# Quasar_v0_1.net
KiCad netlist of a schematic drawn in EAGLE
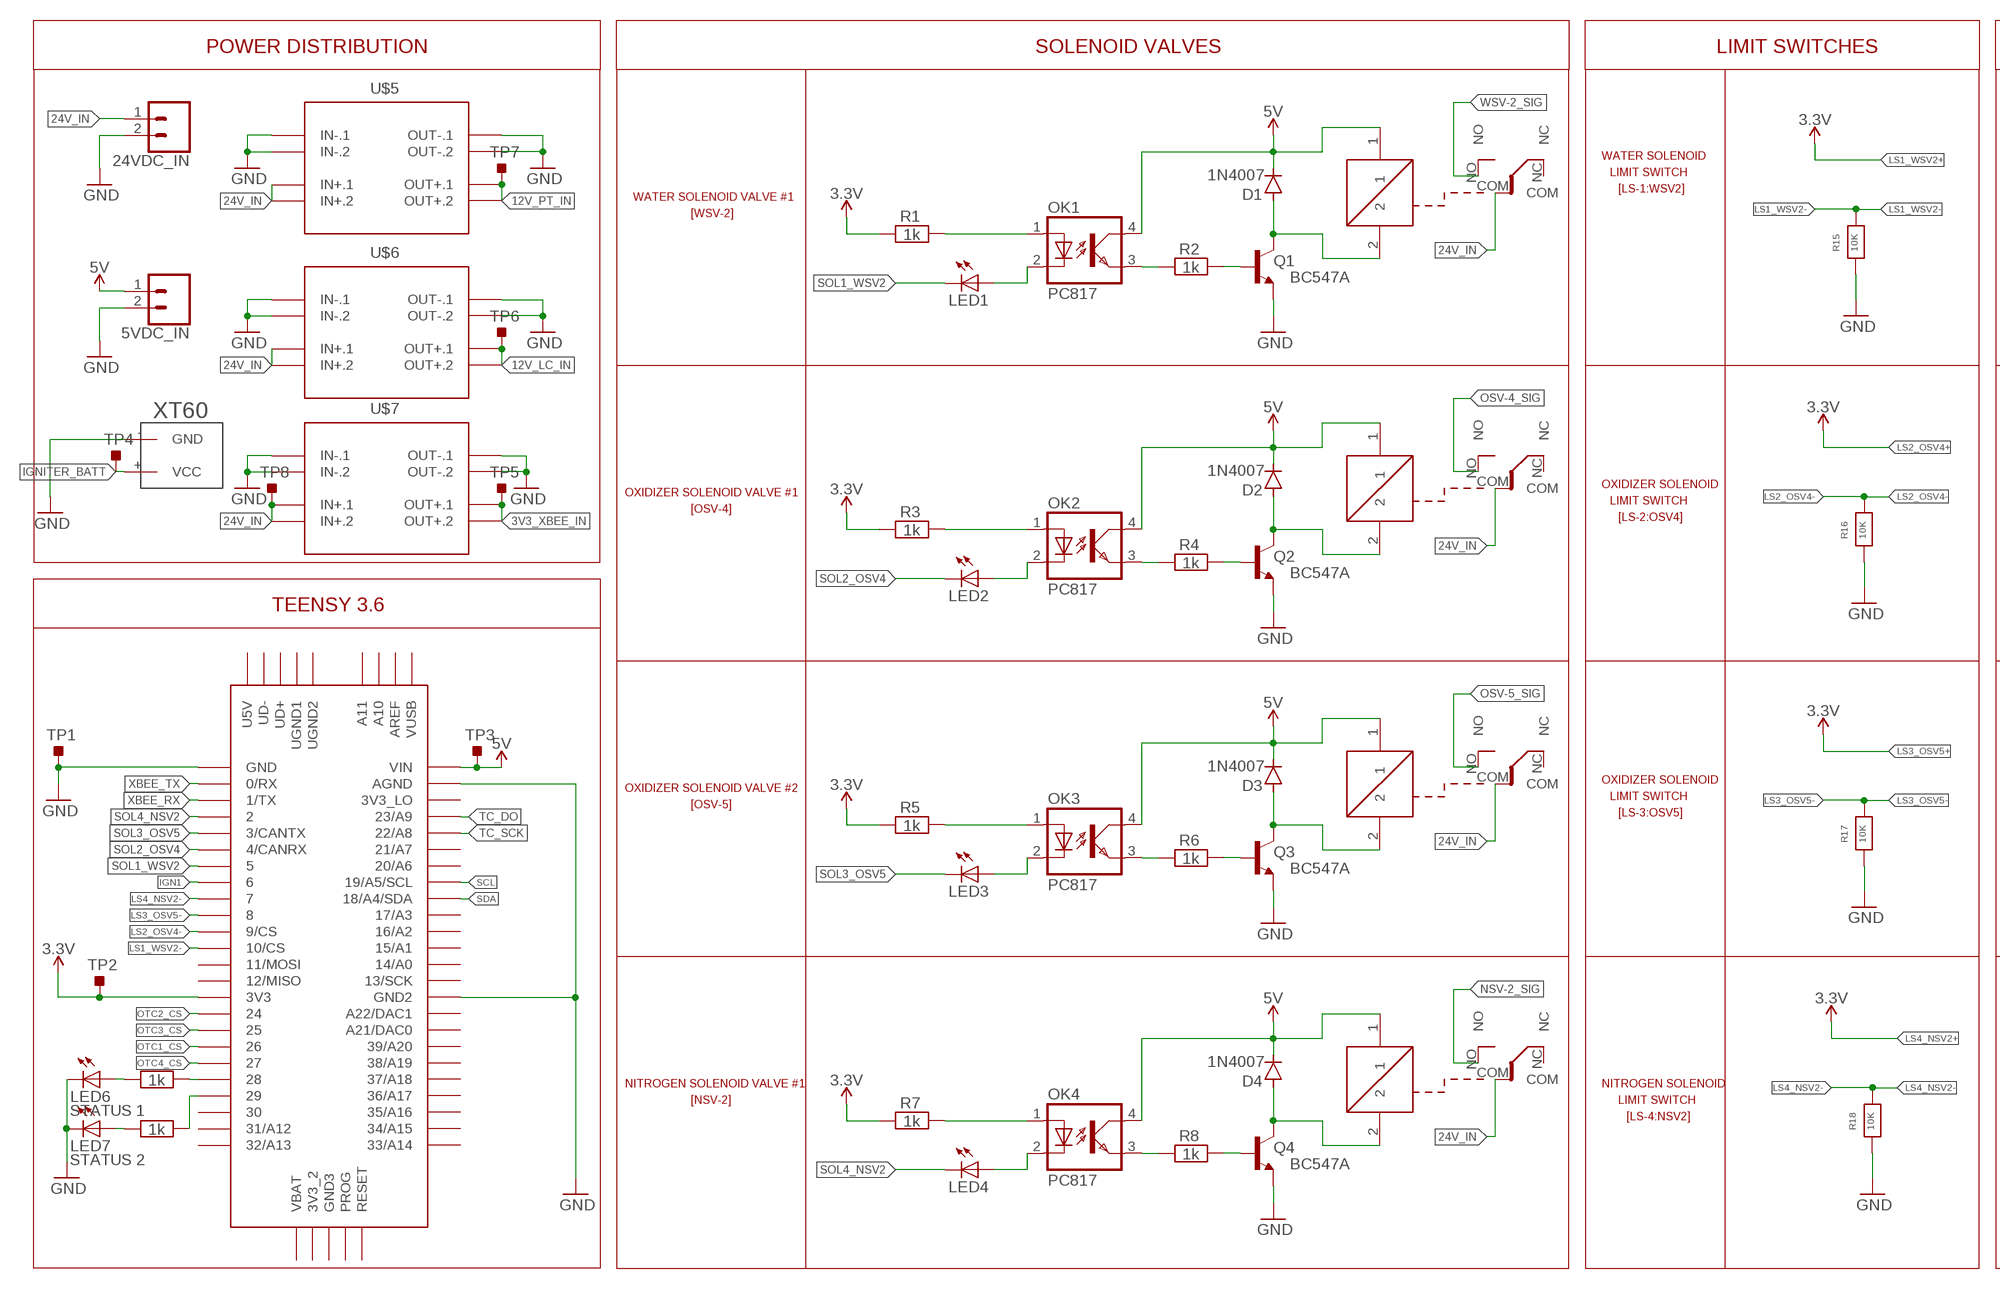
[diagram p0: schematic, sheet 1, part 1 of 2]
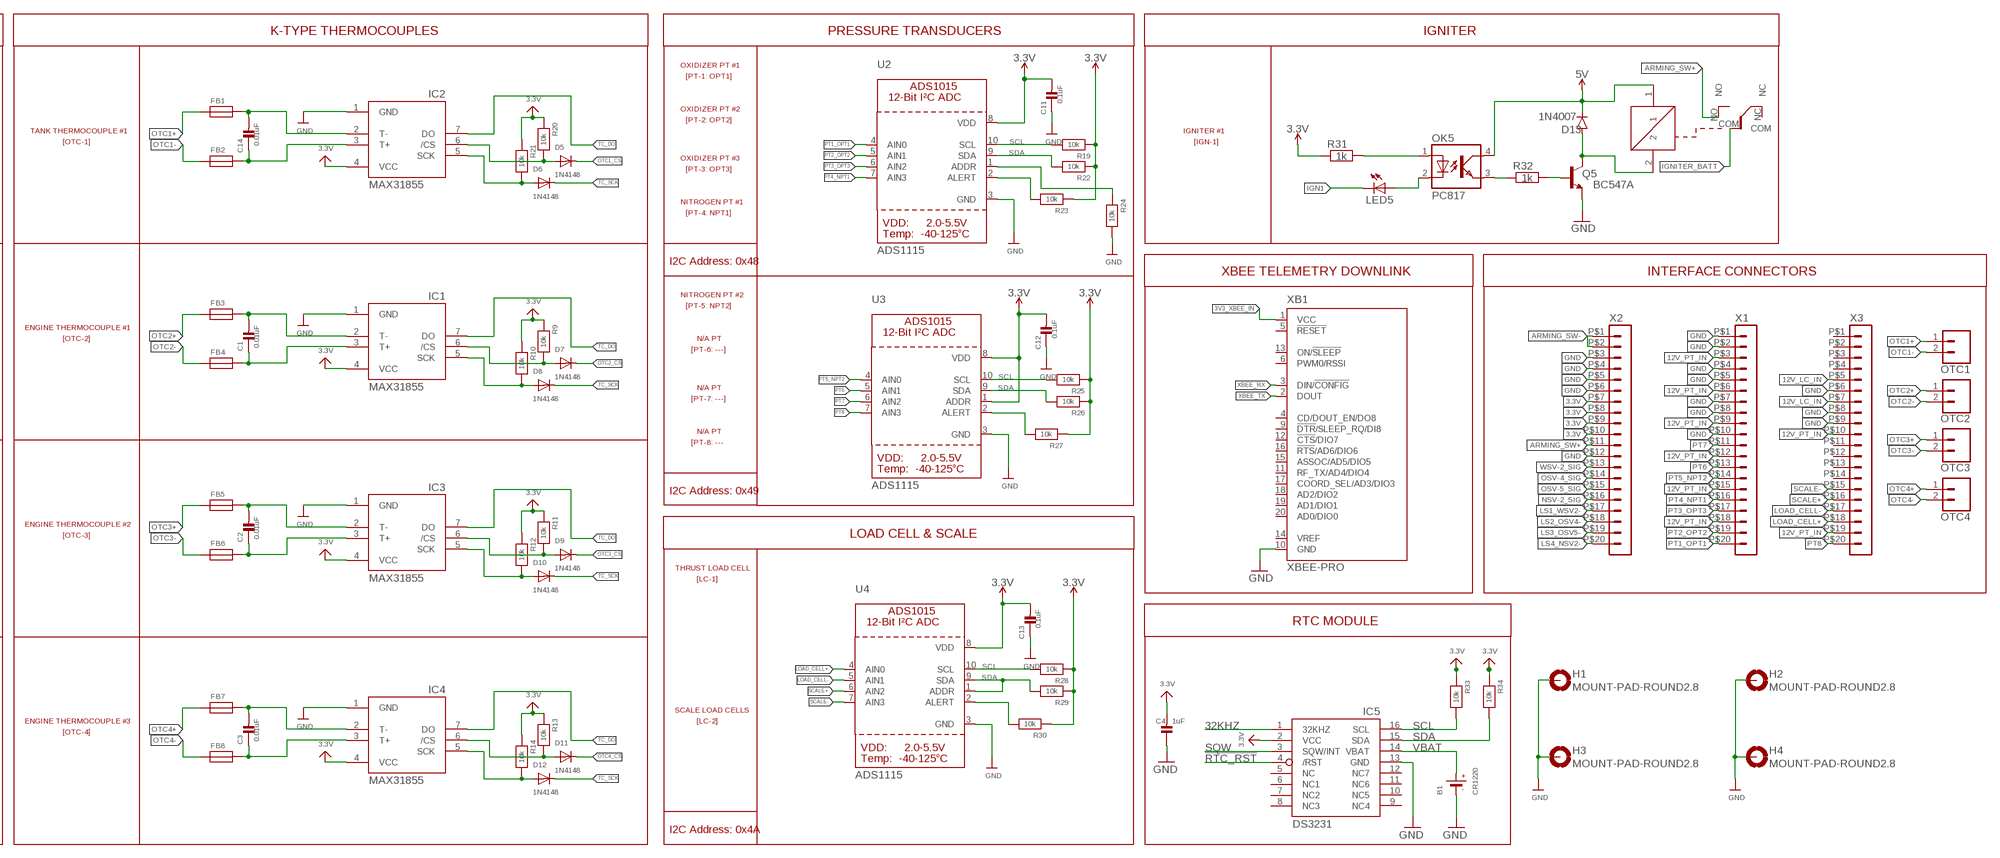
[diagram p1: schematic, sheet 1, part 2 of 2]

(export (version "E")
  (design (tool "Eeschema 10.0.6"))
  (components
    (comp (ref "5VDC_IN")
      (value "CONN_025MM")
      (footprint "eagle-import:SCREWTERMINAL-5MM-2")
      (libsource (lib "eagle-import") (part "CONN_025MM"))
    )
    (comp (ref "24VDC_IN")
      (value "CONN_025MM")
      (footprint "eagle-import:SCREWTERMINAL-5MM-2")
      (libsource (lib "eagle-import") (part "CONN_025MM"))
    )
    (comp (ref "B1")
      (value "CR1220")
      (footprint "eagle-import:CR1220")
      (libsource (lib "eagle-import") (part "BATTERYCR1220_SMT"))
    )
    (comp (ref "C1")
      (value "0.01uF")
      (footprint "eagle-import:0805")
      (libsource (lib "eagle-import") (part "CAP_CERAMIC0805"))
    )
    (comp (ref "C2")
      (value "0.01uF")
      (footprint "eagle-import:0805")
      (libsource (lib "eagle-import") (part "CAP_CERAMIC0805"))
    )
    (comp (ref "C3")
      (value "0.01uF")
      (footprint "eagle-import:0805")
      (libsource (lib "eagle-import") (part "CAP_CERAMIC0805"))
    )
    (comp (ref "C4")
      (value "1uF")
      (footprint "eagle-import:0805")
      (libsource (lib "eagle-import") (part "CAP_CERAMIC0805"))
    )
    (comp (ref "C11")
      (value "0.1uF")
      (footprint "eagle-import:0805")
      (libsource (lib "eagle-import") (part "CAP_CERAMIC0805"))
    )
    (comp (ref "C12")
      (value "0.1uF")
      (footprint "eagle-import:0805")
      (libsource (lib "eagle-import") (part "CAP_CERAMIC0805"))
    )
    (comp (ref "C13")
      (value "0.1uF")
      (footprint "eagle-import:0805")
      (libsource (lib "eagle-import") (part "CAP_CERAMIC0805"))
    )
    (comp (ref "C14")
      (value "0.01uF")
      (footprint "eagle-import:0805")
      (libsource (lib "eagle-import") (part "CAP_CERAMIC0805"))
    )
    (comp (ref "D1")
      (value "1N4007")
      (footprint "eagle-import:DO-41")
      (fields
        (field (name "DIGIKEY_PART_NUMBER") "1N4007MSCT-ND")
        (field (name "MANUFACTURER") "Micro Commercial Co")
        (field (name "CREATED_BY") "PCBLayout.com")
      )
      (libsource (lib "eagle-import") (part "1N4007"))
    )
    (comp (ref "D2")
      (value "1N4007")
      (footprint "eagle-import:DO-41")
      (fields
        (field (name "DIGIKEY_PART_NUMBER") "1N4007MSCT-ND")
        (field (name "MANUFACTURER") "Micro Commercial Co")
        (field (name "CREATED_BY") "PCBLayout.com")
      )
      (libsource (lib "eagle-import") (part "1N4007"))
    )
    (comp (ref "D3")
      (value "1N4007")
      (footprint "eagle-import:DO-41")
      (fields
        (field (name "DIGIKEY_PART_NUMBER") "1N4007MSCT-ND")
        (field (name "MANUFACTURER") "Micro Commercial Co")
        (field (name "CREATED_BY") "PCBLayout.com")
      )
      (libsource (lib "eagle-import") (part "1N4007"))
    )
    (comp (ref "D4")
      (value "1N4007")
      (footprint "eagle-import:DO-41")
      (fields
        (field (name "DIGIKEY_PART_NUMBER") "1N4007MSCT-ND")
        (field (name "MANUFACTURER") "Micro Commercial Co")
        (field (name "CREATED_BY") "PCBLayout.com")
      )
      (libsource (lib "eagle-import") (part "1N4007"))
    )
    (comp (ref "D5")
      (value "1N4148")
      (footprint "eagle-import:SOD-123")
      (libsource (lib "eagle-import") (part "DIODESOD-123"))
    )
    (comp (ref "D6")
      (value "1N4148")
      (footprint "eagle-import:SOD-123")
      (libsource (lib "eagle-import") (part "DIODESOD-123"))
    )
    (comp (ref "D7")
      (value "1N4148")
      (footprint "eagle-import:SOD-123")
      (libsource (lib "eagle-import") (part "DIODESOD-123"))
    )
    (comp (ref "D8")
      (value "1N4148")
      (footprint "eagle-import:SOD-123")
      (libsource (lib "eagle-import") (part "DIODESOD-123"))
    )
    (comp (ref "D9")
      (value "1N4148")
      (footprint "eagle-import:SOD-123")
      (libsource (lib "eagle-import") (part "DIODESOD-123"))
    )
    (comp (ref "D10")
      (value "1N4148")
      (footprint "eagle-import:SOD-123")
      (libsource (lib "eagle-import") (part "DIODESOD-123"))
    )
    (comp (ref "D11")
      (value "1N4148")
      (footprint "eagle-import:SOD-123")
      (libsource (lib "eagle-import") (part "DIODESOD-123"))
    )
    (comp (ref "D12")
      (value "1N4148")
      (footprint "eagle-import:SOD-123")
      (libsource (lib "eagle-import") (part "DIODESOD-123"))
    )
    (comp (ref "D13")
      (value "1N4007")
      (footprint "eagle-import:DO-41")
      (fields
        (field (name "DIGIKEY_PART_NUMBER") "1N4007MSCT-ND")
        (field (name "MANUFACTURER") "Micro Commercial Co")
        (field (name "CREATED_BY") "PCBLayout.com")
      )
      (libsource (lib "eagle-import") (part "1N4007"))
    )
    (comp (ref "FB1")
      (value "FERRITE")
      (footprint "eagle-import:0603")
      (libsource (lib "eagle-import") (part "FERRITE"))
    )
    (comp (ref "FB2")
      (value "FERRITE")
      (footprint "eagle-import:0603")
      (libsource (lib "eagle-import") (part "FERRITE"))
    )
    (comp (ref "FB3")
      (value "FERRITE")
      (footprint "eagle-import:0603")
      (libsource (lib "eagle-import") (part "FERRITE"))
    )
    (comp (ref "FB4")
      (value "FERRITE")
      (footprint "eagle-import:0603")
      (libsource (lib "eagle-import") (part "FERRITE"))
    )
    (comp (ref "FB5")
      (value "FERRITE")
      (footprint "eagle-import:0603")
      (libsource (lib "eagle-import") (part "FERRITE"))
    )
    (comp (ref "FB6")
      (value "FERRITE")
      (footprint "eagle-import:0603")
      (libsource (lib "eagle-import") (part "FERRITE"))
    )
    (comp (ref "FB7")
      (value "FERRITE")
      (footprint "eagle-import:0603")
      (libsource (lib "eagle-import") (part "FERRITE"))
    )
    (comp (ref "FB8")
      (value "FERRITE")
      (footprint "eagle-import:0603")
      (libsource (lib "eagle-import") (part "FERRITE"))
    )
    (comp (ref "H1")
      (value "MOUNT-PAD-ROUND2.8")
      (footprint "eagle-import:2,8-PAD")
      (libsource (lib "eagle-import") (part "MOUNT-PAD-ROUND2.8"))
    )
    (comp (ref "H2")
      (value "MOUNT-PAD-ROUND2.8")
      (footprint "eagle-import:2,8-PAD")
      (libsource (lib "eagle-import") (part "MOUNT-PAD-ROUND2.8"))
    )
    (comp (ref "H3")
      (value "MOUNT-PAD-ROUND2.8")
      (footprint "eagle-import:2,8-PAD")
      (libsource (lib "eagle-import") (part "MOUNT-PAD-ROUND2.8"))
    )
    (comp (ref "H4")
      (value "MOUNT-PAD-ROUND2.8")
      (footprint "eagle-import:2,8-PAD")
      (libsource (lib "eagle-import") (part "MOUNT-PAD-ROUND2.8"))
    )
    (comp (ref "IC1")
      (value "MAX31855")
      (footprint "eagle-import:SO08")
      (libsource (lib "eagle-import") (part "MAX6675"))
    )
    (comp (ref "IC2")
      (value "MAX31855")
      (footprint "eagle-import:SO08")
      (libsource (lib "eagle-import") (part "MAX6675"))
    )
    (comp (ref "IC3")
      (value "MAX31855")
      (footprint "eagle-import:SO08")
      (libsource (lib "eagle-import") (part "MAX6675"))
    )
    (comp (ref "IC4")
      (value "MAX31855")
      (footprint "eagle-import:SO08")
      (libsource (lib "eagle-import") (part "MAX6675"))
    )
    (comp (ref "IC5")
      (value "DS3231/SO")
      (footprint "eagle-import:SO16W")
      (libsource (lib "eagle-import") (part "DS3231/SO"))
    )
    (comp (ref "LED1")
      (value "LEDCHIPLED_1206")
      (footprint "eagle-import:CHIPLED_1206")
      (libsource (lib "eagle-import") (part "adafruit_420_LEDCHIPLED_1206"))
    )
    (comp (ref "LED2")
      (value "LEDCHIPLED_1206")
      (footprint "eagle-import:CHIPLED_1206")
      (libsource (lib "eagle-import") (part "adafruit_420_LEDCHIPLED_1206"))
    )
    (comp (ref "LED3")
      (value "LEDCHIPLED_1206")
      (footprint "eagle-import:CHIPLED_1206")
      (libsource (lib "eagle-import") (part "adafruit_420_LEDCHIPLED_1206"))
    )
    (comp (ref "LED4")
      (value "LEDCHIPLED_1206")
      (footprint "eagle-import:CHIPLED_1206")
      (libsource (lib "eagle-import") (part "adafruit_420_LEDCHIPLED_1206"))
    )
    (comp (ref "LED5")
      (value "LEDCHIPLED_1206")
      (footprint "eagle-import:CHIPLED_1206")
      (libsource (lib "eagle-import") (part "adafruit_420_LEDCHIPLED_1206"))
    )
    (comp (ref "LED6")
      (value "STATUS 1")
      (footprint "eagle-import:LED5MM")
      (libsource (lib "eagle-import") (part "LED5MM"))
    )
    (comp (ref "LED7")
      (value "STATUS 2")
      (footprint "eagle-import:LED5MM")
      (libsource (lib "eagle-import") (part "LED5MM"))
    )
    (comp (ref "OK1")
      (value "PC817")
      (footprint "eagle-import:DIL04")
      (libsource (lib "eagle-import") (part "PC817"))
    )
    (comp (ref "OK2")
      (value "PC817")
      (footprint "eagle-import:DIL04")
      (libsource (lib "eagle-import") (part "PC817"))
    )
    (comp (ref "OK3")
      (value "PC817")
      (footprint "eagle-import:DIL04")
      (libsource (lib "eagle-import") (part "PC817"))
    )
    (comp (ref "OK4")
      (value "PC817")
      (footprint "eagle-import:DIL04")
      (libsource (lib "eagle-import") (part "PC817"))
    )
    (comp (ref "OK5")
      (value "PC817")
      (footprint "eagle-import:DIL04")
      (libsource (lib "eagle-import") (part "PC817"))
    )
    (comp (ref "OTC1")
      (value "CONN_025MM")
      (footprint "eagle-import:SCREWTERMINAL-5MM-2")
      (libsource (lib "eagle-import") (part "CONN_025MM"))
    )
    (comp (ref "OTC2")
      (value "CONN_025MM")
      (footprint "eagle-import:SCREWTERMINAL-5MM-2")
      (libsource (lib "eagle-import") (part "CONN_025MM"))
    )
    (comp (ref "OTC3")
      (value "CONN_025MM")
      (footprint "eagle-import:SCREWTERMINAL-5MM-2")
      (libsource (lib "eagle-import") (part "CONN_025MM"))
    )
    (comp (ref "OTC4")
      (value "CONN_025MM")
      (footprint "eagle-import:SCREWTERMINAL-5MM-2")
      (libsource (lib "eagle-import") (part "CONN_025MM"))
    )
    (comp (ref "Q1")
      (value "BC547A")
      (footprint "eagle-import:TO92")
      (libsource (lib "eagle-import") (part "BC547A"))
    )
    (comp (ref "Q2")
      (value "BC547A")
      (footprint "eagle-import:TO92")
      (libsource (lib "eagle-import") (part "BC547A"))
    )
    (comp (ref "Q3")
      (value "BC547A")
      (footprint "eagle-import:TO92")
      (libsource (lib "eagle-import") (part "BC547A"))
    )
    (comp (ref "Q4")
      (value "BC547A")
      (footprint "eagle-import:TO92")
      (libsource (lib "eagle-import") (part "BC547A"))
    )
    (comp (ref "Q5")
      (value "BC547A")
      (footprint "eagle-import:TO92")
      (libsource (lib "eagle-import") (part "BC547A"))
    )
    (comp (ref "R1")
      (value "1k")
      (footprint "eagle-import:0805")
      (libsource (lib "eagle-import") (part "RESISTOR0805"))
    )
    (comp (ref "R2")
      (value "1k")
      (footprint "eagle-import:0805")
      (libsource (lib "eagle-import") (part "RESISTOR0805"))
    )
    (comp (ref "R3")
      (value "1k")
      (footprint "eagle-import:0805")
      (libsource (lib "eagle-import") (part "RESISTOR0805"))
    )
    (comp (ref "R4")
      (value "1k")
      (footprint "eagle-import:0805")
      (libsource (lib "eagle-import") (part "RESISTOR0805"))
    )
    (comp (ref "R5")
      (value "1k")
      (footprint "eagle-import:0805")
      (libsource (lib "eagle-import") (part "RESISTOR0805"))
    )
    (comp (ref "R6")
      (value "1k")
      (footprint "eagle-import:0805")
      (libsource (lib "eagle-import") (part "RESISTOR0805"))
    )
    (comp (ref "R7")
      (value "1k")
      (footprint "eagle-import:0805")
      (libsource (lib "eagle-import") (part "RESISTOR0805"))
    )
    (comp (ref "R8")
      (value "1k")
      (footprint "eagle-import:0805")
      (libsource (lib "eagle-import") (part "RESISTOR0805"))
    )
    (comp (ref "R9")
      (value "10k")
      (footprint "eagle-import:0805")
      (libsource (lib "eagle-import") (part "RESISTOR0805"))
    )
    (comp (ref "R10")
      (value "10k")
      (footprint "eagle-import:0805")
      (libsource (lib "eagle-import") (part "RESISTOR0805"))
    )
    (comp (ref "R11")
      (value "10k")
      (footprint "eagle-import:0805")
      (libsource (lib "eagle-import") (part "RESISTOR0805"))
    )
    (comp (ref "R12")
      (value "10k")
      (footprint "eagle-import:0805")
      (libsource (lib "eagle-import") (part "RESISTOR0805"))
    )
    (comp (ref "R13")
      (value "10k")
      (footprint "eagle-import:0805")
      (libsource (lib "eagle-import") (part "RESISTOR0805"))
    )
    (comp (ref "R14")
      (value "10k")
      (footprint "eagle-import:0805")
      (libsource (lib "eagle-import") (part "RESISTOR0805"))
    )
    (comp (ref "R15")
      (value "10K")
      (footprint "eagle-import:0805")
      (libsource (lib "eagle-import") (part "RESISTOR0805"))
    )
    (comp (ref "R16")
      (value "10K")
      (footprint "eagle-import:0805")
      (libsource (lib "eagle-import") (part "RESISTOR0805"))
    )
    (comp (ref "R17")
      (value "10K")
      (footprint "eagle-import:0805")
      (libsource (lib "eagle-import") (part "RESISTOR0805"))
    )
    (comp (ref "R18")
      (value "10K")
      (footprint "eagle-import:0805")
      (libsource (lib "eagle-import") (part "RESISTOR0805"))
    )
    (comp (ref "R19")
      (value "10k")
      (footprint "eagle-import:0805")
      (libsource (lib "eagle-import") (part "RESISTOR0805"))
    )
    (comp (ref "R20")
      (value "10k")
      (footprint "eagle-import:0805")
      (libsource (lib "eagle-import") (part "RESISTOR0805"))
    )
    (comp (ref "R21")
      (value "10k")
      (footprint "eagle-import:0805")
      (libsource (lib "eagle-import") (part "RESISTOR0805"))
    )
    (comp (ref "R22")
      (value "10k")
      (footprint "eagle-import:0805")
      (libsource (lib "eagle-import") (part "RESISTOR0805"))
    )
    (comp (ref "R23")
      (value "10k")
      (footprint "eagle-import:0805")
      (libsource (lib "eagle-import") (part "RESISTOR0805"))
    )
    (comp (ref "R24")
      (value "10k")
      (footprint "eagle-import:0805")
      (libsource (lib "eagle-import") (part "RESISTOR0805"))
    )
    (comp (ref "R25")
      (value "10k")
      (footprint "eagle-import:0805")
      (libsource (lib "eagle-import") (part "RESISTOR0805"))
    )
    (comp (ref "R26")
      (value "10k")
      (footprint "eagle-import:0805")
      (libsource (lib "eagle-import") (part "RESISTOR0805"))
    )
    (comp (ref "R27")
      (value "10k")
      (footprint "eagle-import:0805")
      (libsource (lib "eagle-import") (part "RESISTOR0805"))
    )
    (comp (ref "R28")
      (value "10k")
      (footprint "eagle-import:0805")
      (libsource (lib "eagle-import") (part "RESISTOR0805"))
    )
    (comp (ref "R29")
      (value "10k")
      (footprint "eagle-import:0805")
      (libsource (lib "eagle-import") (part "RESISTOR0805"))
    )
    (comp (ref "R30")
      (value "10k")
      (footprint "eagle-import:0805")
      (libsource (lib "eagle-import") (part "RESISTOR0805"))
    )
    (comp (ref "R31")
      (value "1k")
      (footprint "eagle-import:0805")
      (libsource (lib "eagle-import") (part "RESISTOR0805"))
    )
    (comp (ref "R32")
      (value "1k")
      (footprint "eagle-import:0805")
      (libsource (lib "eagle-import") (part "RESISTOR0805"))
    )
    (comp (ref "R33")
      (value "10k")
      (footprint "eagle-import:0805")
      (libsource (lib "eagle-import") (part "RESISTOR0805"))
    )
    (comp (ref "R34")
      (value "10k")
      (footprint "eagle-import:0805")
      (libsource (lib "eagle-import") (part "RESISTOR0805"))
    )
    (comp (ref "R35")
      (value "1k")
      (footprint "eagle-import:0805")
      (libsource (lib "eagle-import") (part "RESISTOR0805"))
    )
    (comp (ref "R36")
      (value "1k")
      (footprint "eagle-import:0805")
      (libsource (lib "eagle-import") (part "RESISTOR0805"))
    )
    (comp (ref "TP1")
      (value "TESTPOINT_TPS-SMD-10SN")
      (footprint "eagle-import:TESTPOINT_SMD-10SN")
      (libsource (lib "eagle-import") (part "TESTPOINT_TPS-SMD-10SN"))
    )
    (comp (ref "TP2")
      (value "TESTPOINT_TPS-SMD-10SN")
      (footprint "eagle-import:TESTPOINT_SMD-10SN")
      (libsource (lib "eagle-import") (part "TESTPOINT_TPS-SMD-10SN"))
    )
    (comp (ref "TP3")
      (value "TESTPOINT_TPS-SMD-10SN")
      (footprint "eagle-import:TESTPOINT_SMD-10SN")
      (libsource (lib "eagle-import") (part "TESTPOINT_TPS-SMD-10SN"))
    )
    (comp (ref "TP4")
      (value "TESTPOINT_TPS-SMD-10SN")
      (footprint "eagle-import:TESTPOINT_SMD-10SN")
      (libsource (lib "eagle-import") (part "TESTPOINT_TPS-SMD-10SN"))
    )
    (comp (ref "TP5")
      (value "TESTPOINT_TPS-SMD-10SN")
      (footprint "eagle-import:TESTPOINT_SMD-10SN")
      (libsource (lib "eagle-import") (part "TESTPOINT_TPS-SMD-10SN"))
    )
    (comp (ref "TP6")
      (value "TESTPOINT_TPS-SMD-10SN")
      (footprint "eagle-import:TESTPOINT_SMD-10SN")
      (libsource (lib "eagle-import") (part "TESTPOINT_TPS-SMD-10SN"))
    )
    (comp (ref "TP7")
      (value "TESTPOINT_TPS-SMD-10SN")
      (footprint "eagle-import:TESTPOINT_SMD-10SN")
      (libsource (lib "eagle-import") (part "TESTPOINT_TPS-SMD-10SN"))
    )
    (comp (ref "TP8")
      (value "TESTPOINT_TPS-SMD-10SN")
      (footprint "eagle-import:TESTPOINT_SMD-10SN")
      (libsource (lib "eagle-import") (part "TESTPOINT_TPS-SMD-10SN"))
    )
    (comp (ref "U$1")
      (value "TEENSY_3.5/3.6")
      (footprint "eagle-import:TEENSY_3.5_3.6")
      (libsource (lib "eagle-import") (part "TEENSY_3.5/3.6"))
    )
    (comp (ref "U$2")
      (value "RW-SH")
      (footprint "eagle-import:RW-SH")
      (libsource (lib "eagle-import") (part "RW-SH"))
    )
    (comp (ref "U$3")
      (value "RW-SH")
      (footprint "eagle-import:RW-SH")
      (libsource (lib "eagle-import") (part "RW-SH"))
    )
    (comp (ref "U$4")
      (value "RW-SH")
      (footprint "eagle-import:RW-SH")
      (libsource (lib "eagle-import") (part "RW-SH"))
    )
    (comp (ref "U$5")
      (value "12V_PT_REG")
      (footprint "eagle-import:DC-DC-STEP-DOWN-MP1584")
      (libsource (lib "eagle-import") (part "DC-DC-STEP-DOWN-MP1584"))
    )
    (comp (ref "U$6")
      (value "12V_LC_REG")
      (footprint "eagle-import:DC-DC-STEP-DOWN-MP1584")
      (libsource (lib "eagle-import") (part "DC-DC-STEP-DOWN-MP1584"))
    )
    (comp (ref "U$7")
      (value "3V3_XBEE_REG")
      (footprint "eagle-import:DC-DC-STEP-DOWN-MP1584")
      (libsource (lib "eagle-import") (part "DC-DC-STEP-DOWN-MP1584"))
    )
    (comp (ref "U$13")
      (value "RW-SH")
      (footprint "eagle-import:RW-SH")
      (libsource (lib "eagle-import") (part "RW-SH"))
    )
    (comp (ref "U$18")
      (value "RW-SH")
      (footprint "eagle-import:RW-SH")
      (libsource (lib "eagle-import") (part "RW-SH"))
    )
    (comp (ref "U$19")
      (value "XT60")
      (footprint "eagle-import:XT60")
      (libsource (lib "eagle-import") (part "XT60"))
    )
    (comp (ref "U2")
      (value "ADS1115")
      (footprint "eagle-import:MSOP10")
      (libsource (lib "eagle-import") (part "ADC_ADS1015"))
    )
    (comp (ref "U3")
      (value "ADS1115")
      (footprint "eagle-import:MSOP10")
      (libsource (lib "eagle-import") (part "ADC_ADS1015"))
    )
    (comp (ref "U4")
      (value "ADS1115")
      (footprint "eagle-import:MSOP10")
      (libsource (lib "eagle-import") (part "ADC_ADS1015"))
    )
    (comp (ref "X1")
      (value "HEADER_POS20_44914-2001")
      (footprint "eagle-import:44914-2001")
      (libsource (lib "eagle-import") (part "HEADER_POS20_?44914-2001"))
    )
    (comp (ref "X2")
      (value "HEADER_POS20_44914-2001")
      (footprint "eagle-import:44914-2001")
      (libsource (lib "eagle-import") (part "HEADER_POS20_?44914-2001"))
    )
    (comp (ref "X3")
      (value "HEADER_POS20_44914-2001")
      (footprint "eagle-import:44914-2001")
      (libsource (lib "eagle-import") (part "HEADER_POS20_?44914-2001"))
    )
    (comp (ref "XB1")
      (value "XBEE-PRO")
      (footprint "eagle-import:XBEE-PRO")
      (fields (field (name "MPN") "XBP24-AWI-001"))
      (libsource (lib "eagle-import") (part "XBEE-PRO"))
    )
  )
  (nets
    (net (code "1") (name "/32KHZ") (class "Default")
      (node (ref "IC5") (pin "1") (pinfunction "32KHZ_1") (pintype "output"))
    )
    (net (code "2") (name "/SQW") (class "Default")
      (node (ref "IC5") (pin "3") (pinfunction "SQW/INT_3") (pintype "output"))
    )
    (net (code "3") (name "/VBAT") (class "Default")
      (node (ref "B1") (pin "+$1") (pinfunction "+_+$1") (pintype "passive"))
      (node (ref "IC5") (pin "14") (pinfunction "VBAT_14") (pintype "power_in"))
    )
    (net (code "4") (name "/~{RTC_RST}") (class "Default")
      (node (ref "IC5") (pin "4") (pinfunction "/RST_4") (pintype "passive"))
    )
    (net (code "5") (name "3.3V") (class "Default")
      (node (ref "C11") (pin "2") (pinfunction "P$2_2") (pintype "passive"))
      (node (ref "C12") (pin "2") (pinfunction "P$2_2") (pintype "passive"))
      (node (ref "C13") (pin "2") (pinfunction "P$2_2") (pintype "passive"))
      (node (ref "C4") (pin "2") (pinfunction "P$2_2") (pintype "passive"))
      (node (ref "IC1") (pin "4") (pinfunction "VCC_4") (pintype "power_in"))
      (node (ref "IC2") (pin "4") (pinfunction "VCC_4") (pintype "power_in"))
      (node (ref "IC3") (pin "4") (pinfunction "VCC_4") (pintype "power_in"))
      (node (ref "IC4") (pin "4") (pinfunction "VCC_4") (pintype "power_in"))
      (node (ref "IC5") (pin "2") (pinfunction "VCC_2") (pintype "power_in"))
      (node (ref "R1") (pin "2") (pinfunction "2_2") (pintype "passive"))
      (node (ref "R10") (pin "1") (pinfunction "1_1") (pintype "passive"))
      (node (ref "R11") (pin "1") (pinfunction "1_1") (pintype "passive"))
      (node (ref "R12") (pin "1") (pinfunction "1_1") (pintype "passive"))
      (node (ref "R13") (pin "1") (pinfunction "1_1") (pintype "passive"))
      (node (ref "R14") (pin "1") (pinfunction "1_1") (pintype "passive"))
      (node (ref "R19") (pin "1") (pinfunction "1_1") (pintype "passive"))
      (node (ref "R20") (pin "1") (pinfunction "1_1") (pintype "passive"))
      (node (ref "R21") (pin "1") (pinfunction "1_1") (pintype "passive"))
      (node (ref "R22") (pin "1") (pinfunction "1_1") (pintype "passive"))
      (node (ref "R23") (pin "1") (pinfunction "1_1") (pintype "passive"))
      (node (ref "R25") (pin "1") (pinfunction "1_1") (pintype "passive"))
      (node (ref "R26") (pin "1") (pinfunction "1_1") (pintype "passive"))
      (node (ref "R27") (pin "1") (pinfunction "1_1") (pintype "passive"))
      (node (ref "R28") (pin "1") (pinfunction "1_1") (pintype "passive"))
      (node (ref "R29") (pin "1") (pinfunction "1_1") (pintype "passive"))
      (node (ref "R3") (pin "2") (pinfunction "2_2") (pintype "passive"))
      (node (ref "R30") (pin "1") (pinfunction "1_1") (pintype "passive"))
      (node (ref "R31") (pin "2") (pinfunction "2_2") (pintype "passive"))
      (node (ref "R33") (pin "1") (pinfunction "1_1") (pintype "passive"))
      (node (ref "R34") (pin "1") (pinfunction "1_1") (pintype "passive"))
      (node (ref "R5") (pin "2") (pinfunction "2_2") (pintype "passive"))
      (node (ref "R7") (pin "2") (pinfunction "2_2") (pintype "passive"))
      (node (ref "R9") (pin "1") (pinfunction "1_1") (pintype "passive"))
      (node (ref "TP2") (pin "TP") (pinfunction "TP_TP") (pintype "passive"))
      (node (ref "U$1") (pin "3V3") (pinfunction "3V3_3V3") (pintype "bidirectional"))
      (node (ref "U2") (pin "8") (pinfunction "VDD_8") (pintype "bidirectional"))
      (node (ref "U3") (pin "1") (pinfunction "ADDR_1") (pintype "bidirectional"))
      (node (ref "U3") (pin "8") (pinfunction "VDD_8") (pintype "bidirectional"))
      (node (ref "U4") (pin "8") (pinfunction "VDD_8") (pintype "bidirectional"))
      (node (ref "X2") (pin "P$10") (pinfunction "10_P$10") (pintype "passive"))
      (node (ref "X2") (pin "P$7") (pinfunction "7_P$7") (pintype "passive"))
      (node (ref "X2") (pin "P$8") (pinfunction "8_P$8") (pintype "passive"))
      (node (ref "X2") (pin "P$9") (pinfunction "9_P$9") (pintype "passive"))
    )
    (net (code "6") (name "3V3_XBEE_IN") (class "Default")
      (node (ref "TP5") (pin "TP") (pinfunction "TP_TP") (pintype "passive"))
      (node (ref "U$7") (pin "OUT+.1") (pinfunction "OUT+.1_OUT+.1") (pintype "bidirectional"))
      (node (ref "U$7") (pin "OUT+.2") (pinfunction "OUT+.2_OUT+.2") (pintype "bidirectional"))
      (node (ref "XB1") (pin "1") (pinfunction "VCC_1") (pintype "power_in"))
    )
    (net (code "7") (name "5V") (class "Default")
      (node (ref "5VDC_IN") (pin "1") (pinfunction "1_1") (pintype "passive"))
      (node (ref "D1") (pin "C") (pinfunction "C_C") (pintype "passive"))
      (node (ref "D13") (pin "C") (pinfunction "C_C") (pintype "passive"))
      (node (ref "D2") (pin "C") (pinfunction "C_C") (pintype "passive"))
      (node (ref "D3") (pin "C") (pinfunction "C_C") (pintype "passive"))
      (node (ref "D4") (pin "C") (pinfunction "C_C") (pintype "passive"))
      (node (ref "OK1") (pin "4") (pinfunction "COL_4") (pintype "passive"))
      (node (ref "OK2") (pin "4") (pinfunction "COL_4") (pintype "passive"))
      (node (ref "OK3") (pin "4") (pinfunction "COL_4") (pintype "passive"))
      (node (ref "OK4") (pin "4") (pinfunction "COL_4") (pintype "passive"))
      (node (ref "OK5") (pin "4") (pinfunction "COL_4") (pintype "passive"))
      (node (ref "TP3") (pin "TP") (pinfunction "TP_TP") (pintype "passive"))
      (node (ref "U$1") (pin "VIN") (pinfunction "VIN_VIN") (pintype "bidirectional"))
      (node (ref "U$13") (pin "1") (pinfunction "1_1") (pintype "bidirectional"))
      (node (ref "U$18") (pin "1") (pinfunction "1_1") (pintype "bidirectional"))
      (node (ref "U$2") (pin "1") (pinfunction "1_1") (pintype "bidirectional"))
      (node (ref "U$3") (pin "1") (pinfunction "1_1") (pintype "bidirectional"))
      (node (ref "U$4") (pin "1") (pinfunction "1_1") (pintype "bidirectional"))
    )
    (net (code "8") (name "12V_LC_IN") (class "Default")
      (node (ref "TP6") (pin "TP") (pinfunction "TP_TP") (pintype "passive"))
      (node (ref "U$6") (pin "OUT+.1") (pinfunction "OUT+.1_OUT+.1") (pintype "bidirectional"))
      (node (ref "U$6") (pin "OUT+.2") (pinfunction "OUT+.2_OUT+.2") (pintype "bidirectional"))
      (node (ref "X3") (pin "P$5") (pinfunction "5_P$5") (pintype "passive"))
      (node (ref "X3") (pin "P$7") (pinfunction "7_P$7") (pintype "passive"))
    )
    (net (code "9") (name "12V_PT_IN") (class "Default")
      (node (ref "TP7") (pin "TP") (pinfunction "TP_TP") (pintype "passive"))
      (node (ref "U$5") (pin "OUT+.1") (pinfunction "OUT+.1_OUT+.1") (pintype "bidirectional"))
      (node (ref "U$5") (pin "OUT+.2") (pinfunction "OUT+.2_OUT+.2") (pintype "bidirectional"))
      (node (ref "X1") (pin "P$12") (pinfunction "12_P$12") (pintype "passive"))
      (node (ref "X1") (pin "P$15") (pinfunction "15_P$15") (pintype "passive"))
      (node (ref "X1") (pin "P$18") (pinfunction "18_P$18") (pintype "passive"))
      (node (ref "X1") (pin "P$3") (pinfunction "3_P$3") (pintype "passive"))
      (node (ref "X1") (pin "P$6") (pinfunction "6_P$6") (pintype "passive"))
      (node (ref "X1") (pin "P$9") (pinfunction "9_P$9") (pintype "passive"))
      (node (ref "X3") (pin "P$10") (pinfunction "10_P$10") (pintype "passive"))
      (node (ref "X3") (pin "P$19") (pinfunction "19_P$19") (pintype "passive"))
    )
    (net (code "10") (name "24V_IN") (class "Default")
      (node (ref "24VDC_IN") (pin "1") (pinfunction "1_1") (pintype "passive"))
      (node (ref "TP8") (pin "TP") (pinfunction "TP_TP") (pintype "passive"))
      (node (ref "U$13") (pin "COM") (pinfunction "COM_COM") (pintype "bidirectional"))
      (node (ref "U$2") (pin "COM") (pinfunction "COM_COM") (pintype "bidirectional"))
      (node (ref "U$3") (pin "COM") (pinfunction "COM_COM") (pintype "bidirectional"))
      (node (ref "U$4") (pin "COM") (pinfunction "COM_COM") (pintype "bidirectional"))
      (node (ref "U$5") (pin "IN+.1") (pinfunction "IN+.1_IN+.1") (pintype "bidirectional"))
      (node (ref "U$5") (pin "IN+.2") (pinfunction "IN+.2_IN+.2") (pintype "bidirectional"))
      (node (ref "U$6") (pin "IN+.1") (pinfunction "IN+.1_IN+.1") (pintype "bidirectional"))
      (node (ref "U$6") (pin "IN+.2") (pinfunction "IN+.2_IN+.2") (pintype "bidirectional"))
      (node (ref "U$7") (pin "IN+.1") (pinfunction "IN+.1_IN+.1") (pintype "bidirectional"))
      (node (ref "U$7") (pin "IN+.2") (pinfunction "IN+.2_IN+.2") (pintype "bidirectional"))
    )
    (net (code "11") (name "ARMING_SW+") (class "Default")
      (node (ref "U$18") (pin "NO") (pinfunction "NO_NO") (pintype "bidirectional"))
      (node (ref "X2") (pin "P$11") (pinfunction "11_P$11") (pintype "passive"))
    )
    (net (code "12") (name "ARMING_SW-") (class "Default")
      (node (ref "X2") (pin "P$1") (pinfunction "1_P$1") (pintype "passive"))
      (node (ref "X2") (pin "P$2") (pinfunction "2_P$2") (pintype "passive"))
    )
    (net (code "13") (name "GND") (class "Default")
      (node (ref "24VDC_IN") (pin "2") (pinfunction "2_2") (pintype "passive"))
      (node (ref "5VDC_IN") (pin "2") (pinfunction "2_2") (pintype "passive"))
      (node (ref "B1") (pin "-") (pinfunction "-_-") (pintype "passive"))
      (node (ref "C11") (pin "1") (pinfunction "P$1_1") (pintype "passive"))
      (node (ref "C12") (pin "1") (pinfunction "P$1_1") (pintype "passive"))
      (node (ref "C13") (pin "1") (pinfunction "P$1_1") (pintype "passive"))
      (node (ref "C4") (pin "1") (pinfunction "P$1_1") (pintype "passive"))
      (node (ref "H1") (pin "B2,8") (pinfunction "MOUNT_B2,8") (pintype "passive"))
      (node (ref "H2") (pin "B2,8") (pinfunction "MOUNT_B2,8") (pintype "passive"))
      (node (ref "H3") (pin "B2,8") (pinfunction "MOUNT_B2,8") (pintype "passive"))
      (node (ref "H4") (pin "B2,8") (pinfunction "MOUNT_B2,8") (pintype "passive"))
      (node (ref "IC1") (pin "1") (pinfunction "GND_1") (pintype "power_in"))
      (node (ref "IC2") (pin "1") (pinfunction "GND_1") (pintype "power_in"))
      (node (ref "IC3") (pin "1") (pinfunction "GND_1") (pintype "power_in"))
      (node (ref "IC4") (pin "1") (pinfunction "GND_1") (pintype "power_in"))
      (node (ref "IC5") (pin "13") (pinfunction "GND_13") (pintype "power_in"))
      (node (ref "LED6") (pin "K") (pinfunction "C_K") (pintype "passive"))
      (node (ref "LED7") (pin "K") (pinfunction "C_K") (pintype "passive"))
      (node (ref "Q1") (pin "1") (pinfunction "E_1") (pintype "passive"))
      (node (ref "Q2") (pin "1") (pinfunction "E_1") (pintype "passive"))
      (node (ref "Q3") (pin "1") (pinfunction "E_1") (pintype "passive"))
      (node (ref "Q4") (pin "1") (pinfunction "E_1") (pintype "passive"))
      (node (ref "Q5") (pin "1") (pinfunction "E_1") (pintype "passive"))
      (node (ref "R15") (pin "2") (pinfunction "2_2") (pintype "passive"))
      (node (ref "R16") (pin "2") (pinfunction "2_2") (pintype "passive"))
      (node (ref "R17") (pin "2") (pinfunction "2_2") (pintype "passive"))
      (node (ref "R18") (pin "2") (pinfunction "2_2") (pintype "passive"))
      (node (ref "R24") (pin "2") (pinfunction "2_2") (pintype "passive"))
      (node (ref "TP1") (pin "TP") (pinfunction "TP_TP") (pintype "passive"))
      (node (ref "U$1") (pin "AGND") (pinfunction "AGND_AGND") (pintype "bidirectional"))
      (node (ref "U$1") (pin "GND") (pinfunction "GND_GND") (pintype "bidirectional"))
      (node (ref "U$1") (pin "GND2") (pinfunction "GND2_GND2") (pintype "bidirectional"))
      (node (ref "U$19") (pin "-") (pinfunction "GND_-") (pintype "bidirectional"))
      (node (ref "U$5") (pin "IN-.1") (pinfunction "IN-.1_IN-.1") (pintype "bidirectional"))
      (node (ref "U$5") (pin "IN-.2") (pinfunction "IN-.2_IN-.2") (pintype "bidirectional"))
      (node (ref "U$5") (pin "OUT-.1") (pinfunction "OUT-.1_OUT-.1") (pintype "bidirectional"))
      (node (ref "U$5") (pin "OUT-.2") (pinfunction "OUT-.2_OUT-.2") (pintype "bidirectional"))
      (node (ref "U$6") (pin "IN-.1") (pinfunction "IN-.1_IN-.1") (pintype "bidirectional"))
      (node (ref "U$6") (pin "IN-.2") (pinfunction "IN-.2_IN-.2") (pintype "bidirectional"))
      (node (ref "U$6") (pin "OUT-.1") (pinfunction "OUT-.1_OUT-.1") (pintype "bidirectional"))
      (node (ref "U$6") (pin "OUT-.2") (pinfunction "OUT-.2_OUT-.2") (pintype "bidirectional"))
      (node (ref "U$7") (pin "IN-.1") (pinfunction "IN-.1_IN-.1") (pintype "bidirectional"))
      (node (ref "U$7") (pin "IN-.2") (pinfunction "IN-.2_IN-.2") (pintype "bidirectional"))
      (node (ref "U$7") (pin "OUT-.1") (pinfunction "OUT-.1_OUT-.1") (pintype "bidirectional"))
      (node (ref "U$7") (pin "OUT-.2") (pinfunction "OUT-.2_OUT-.2") (pintype "bidirectional"))
      (node (ref "U2") (pin "3") (pinfunction "GND_3") (pintype "bidirectional"))
      (node (ref "U3") (pin "3") (pinfunction "GND_3") (pintype "bidirectional"))
      (node (ref "U4") (pin "3") (pinfunction "GND_3") (pintype "bidirectional"))
      (node (ref "X1") (pin "P$1") (pinfunction "1_P$1") (pintype "passive"))
      (node (ref "X1") (pin "P$10") (pinfunction "10_P$10") (pintype "passive"))
      (node (ref "X1") (pin "P$2") (pinfunction "2_P$2") (pintype "passive"))
      (node (ref "X1") (pin "P$4") (pinfunction "4_P$4") (pintype "passive"))
      (node (ref "X1") (pin "P$5") (pinfunction "5_P$5") (pintype "passive"))
      (node (ref "X1") (pin "P$7") (pinfunction "7_P$7") (pintype "passive"))
      (node (ref "X1") (pin "P$8") (pinfunction "8_P$8") (pintype "passive"))
      (node (ref "X2") (pin "P$12") (pinfunction "12_P$12") (pintype "passive"))
      (node (ref "X2") (pin "P$3") (pinfunction "3_P$3") (pintype "passive"))
      (node (ref "X2") (pin "P$4") (pinfunction "4_P$4") (pintype "passive"))
      (node (ref "X2") (pin "P$5") (pinfunction "5_P$5") (pintype "passive"))
      (node (ref "X2") (pin "P$6") (pinfunction "6_P$6") (pintype "passive"))
      (node (ref "X3") (pin "P$6") (pinfunction "6_P$6") (pintype "passive"))
      (node (ref "X3") (pin "P$8") (pinfunction "8_P$8") (pintype "passive"))
      (node (ref "X3") (pin "P$9") (pinfunction "9_P$9") (pintype "passive"))
      (node (ref "XB1") (pin "10") (pinfunction "GND_10") (pintype "power_in"))
    )
    (net (code "14") (name "IGN1") (class "Default")
      (node (ref "LED5") (pin "C") (pinfunction "C_C") (pintype "passive"))
      (node (ref "U$1") (pin "6") (pinfunction "6_6") (pintype "bidirectional"))
    )
    (net (code "15") (name "IGNITER_BATT") (class "Default")
      (node (ref "TP4") (pin "TP") (pinfunction "TP_TP") (pintype "passive"))
      (node (ref "U$18") (pin "COM") (pinfunction "COM_COM") (pintype "bidirectional"))
      (node (ref "U$19") (pin "+") (pinfunction "VCC_+") (pintype "bidirectional"))
    )
    (net (code "16") (name "LOAD_CELL+") (class "Default")
      (node (ref "U4") (pin "4") (pinfunction "AIN0_4") (pintype "bidirectional"))
      (node (ref "X3") (pin "P$18") (pinfunction "18_P$18") (pintype "passive"))
    )
    (net (code "17") (name "LOAD_CELL-") (class "Default")
      (node (ref "U4") (pin "5") (pinfunction "AIN1_5") (pintype "bidirectional"))
      (node (ref "X3") (pin "P$17") (pinfunction "17_P$17") (pintype "passive"))
    )
    (net (code "18") (name "LS1_WSV2-") (class "Default")
      (node (ref "R15") (pin "1") (pinfunction "1_1") (pintype "passive"))
      (node (ref "U$1") (pin "10/CS") (pinfunction "10/CS_10/CS") (pintype "bidirectional"))
      (node (ref "X2") (pin "P$17") (pinfunction "17_P$17") (pintype "passive"))
    )
    (net (code "19") (name "LS2_OSV4-") (class "Default")
      (node (ref "R16") (pin "1") (pinfunction "1_1") (pintype "passive"))
      (node (ref "U$1") (pin "9/CS") (pinfunction "9/CS_9/CS") (pintype "bidirectional"))
      (node (ref "X2") (pin "P$18") (pinfunction "18_P$18") (pintype "passive"))
    )
    (net (code "20") (name "LS3_OSV5-") (class "Default")
      (node (ref "R17") (pin "1") (pinfunction "1_1") (pintype "passive"))
      (node (ref "U$1") (pin "8") (pinfunction "8_8") (pintype "bidirectional"))
      (node (ref "X2") (pin "P$19") (pinfunction "19_P$19") (pintype "passive"))
    )
    (net (code "21") (name "LS4_NSV2-") (class "Default")
      (node (ref "R18") (pin "1") (pinfunction "1_1") (pintype "passive"))
      (node (ref "U$1") (pin "7") (pinfunction "7_7") (pintype "bidirectional"))
      (node (ref "X2") (pin "P$20") (pinfunction "20_P$20") (pintype "passive"))
    )
    (net (code "22") (name "NSV-2_SIG") (class "Default")
      (node (ref "U$4") (pin "NO") (pinfunction "NO_NO") (pintype "bidirectional"))
      (node (ref "X2") (pin "P$16") (pinfunction "16_P$16") (pintype "passive"))
    )
    (net (code "23") (name "Net-(C1-P$1)") (class "Default")
      (node (ref "C1") (pin "1") (pinfunction "P$1_1") (pintype "passive"))
      (node (ref "FB4") (pin "2") (pinfunction "P$2_2") (pintype "bidirectional"))
      (node (ref "IC1") (pin "3") (pinfunction "T+_3") (pintype "input"))
    )
    (net (code "24") (name "Net-(C1-P$2)") (class "Default")
      (node (ref "C1") (pin "2") (pinfunction "P$2_2") (pintype "passive"))
      (node (ref "FB3") (pin "2") (pinfunction "P$2_2") (pintype "bidirectional"))
      (node (ref "IC1") (pin "2") (pinfunction "T-_2") (pintype "input"))
    )
    (net (code "25") (name "Net-(C2-P$1)") (class "Default")
      (node (ref "C2") (pin "1") (pinfunction "P$1_1") (pintype "passive"))
      (node (ref "FB6") (pin "2") (pinfunction "P$2_2") (pintype "bidirectional"))
      (node (ref "IC3") (pin "3") (pinfunction "T+_3") (pintype "input"))
    )
    (net (code "26") (name "Net-(C2-P$2)") (class "Default")
      (node (ref "C2") (pin "2") (pinfunction "P$2_2") (pintype "passive"))
      (node (ref "FB5") (pin "2") (pinfunction "P$2_2") (pintype "bidirectional"))
      (node (ref "IC3") (pin "2") (pinfunction "T-_2") (pintype "input"))
    )
    (net (code "27") (name "Net-(C3-P$1)") (class "Default")
      (node (ref "C3") (pin "1") (pinfunction "P$1_1") (pintype "passive"))
      (node (ref "FB8") (pin "2") (pinfunction "P$2_2") (pintype "bidirectional"))
      (node (ref "IC4") (pin "3") (pinfunction "T+_3") (pintype "input"))
    )
    (net (code "28") (name "Net-(C3-P$2)") (class "Default")
      (node (ref "C3") (pin "2") (pinfunction "P$2_2") (pintype "passive"))
      (node (ref "FB7") (pin "2") (pinfunction "P$2_2") (pintype "bidirectional"))
      (node (ref "IC4") (pin "2") (pinfunction "T-_2") (pintype "input"))
    )
    (net (code "29") (name "Net-(C14-P$1)") (class "Default")
      (node (ref "C14") (pin "1") (pinfunction "P$1_1") (pintype "passive"))
      (node (ref "FB2") (pin "2") (pinfunction "P$2_2") (pintype "bidirectional"))
      (node (ref "IC2") (pin "3") (pinfunction "T+_3") (pintype "input"))
    )
    (net (code "30") (name "Net-(C14-P$2)") (class "Default")
      (node (ref "C14") (pin "2") (pinfunction "P$2_2") (pintype "passive"))
      (node (ref "FB1") (pin "2") (pinfunction "P$2_2") (pintype "bidirectional"))
      (node (ref "IC2") (pin "2") (pinfunction "T-_2") (pintype "input"))
    )
    (net (code "31") (name "Net-(IC1-SCK)") (class "Default")
      (node (ref "D8") (pin "A") (pinfunction "A_A") (pintype "passive"))
      (node (ref "IC1") (pin "5") (pinfunction "SCK_5") (pintype "input"))
      (node (ref "R10") (pin "2") (pinfunction "2_2") (pintype "passive"))
    )
    (net (code "32") (name "Net-(IC1-{slash}CS)") (class "Default")
      (node (ref "D7") (pin "A") (pinfunction "A_A") (pintype "passive"))
      (node (ref "IC1") (pin "6") (pinfunction "/CS_6") (pintype "input"))
      (node (ref "R9") (pin "2") (pinfunction "2_2") (pintype "passive"))
    )
    (net (code "33") (name "Net-(IC2-SCK)") (class "Default")
      (node (ref "D6") (pin "A") (pinfunction "A_A") (pintype "passive"))
      (node (ref "IC2") (pin "5") (pinfunction "SCK_5") (pintype "input"))
      (node (ref "R21") (pin "2") (pinfunction "2_2") (pintype "passive"))
    )
    (net (code "34") (name "Net-(IC2-{slash}CS)") (class "Default")
      (node (ref "D5") (pin "A") (pinfunction "A_A") (pintype "passive"))
      (node (ref "IC2") (pin "6") (pinfunction "/CS_6") (pintype "input"))
      (node (ref "R20") (pin "2") (pinfunction "2_2") (pintype "passive"))
    )
    (net (code "35") (name "Net-(IC3-SCK)") (class "Default")
      (node (ref "D10") (pin "A") (pinfunction "A_A") (pintype "passive"))
      (node (ref "IC3") (pin "5") (pinfunction "SCK_5") (pintype "input"))
      (node (ref "R12") (pin "2") (pinfunction "2_2") (pintype "passive"))
    )
    (net (code "36") (name "Net-(IC3-{slash}CS)") (class "Default")
      (node (ref "D9") (pin "A") (pinfunction "A_A") (pintype "passive"))
      (node (ref "IC3") (pin "6") (pinfunction "/CS_6") (pintype "input"))
      (node (ref "R11") (pin "2") (pinfunction "2_2") (pintype "passive"))
    )
    (net (code "37") (name "Net-(IC4-SCK)") (class "Default")
      (node (ref "D12") (pin "A") (pinfunction "A_A") (pintype "passive"))
      (node (ref "IC4") (pin "5") (pinfunction "SCK_5") (pintype "input"))
      (node (ref "R14") (pin "2") (pinfunction "2_2") (pintype "passive"))
    )
    (net (code "38") (name "Net-(IC4-{slash}CS)") (class "Default")
      (node (ref "D11") (pin "A") (pinfunction "A_A") (pintype "passive"))
      (node (ref "IC4") (pin "6") (pinfunction "/CS_6") (pintype "input"))
      (node (ref "R13") (pin "2") (pinfunction "2_2") (pintype "passive"))
    )
    (net (code "39") (name "Net-(LED6-PadA)") (class "Default")
      (node (ref "LED6") (pin "A") (pinfunction "A_A") (pintype "passive"))
      (node (ref "R35") (pin "2") (pinfunction "2_2") (pintype "passive"))
    )
    (net (code "40") (name "Net-(LED7-PadA)") (class "Default")
      (node (ref "LED7") (pin "A") (pinfunction "A_A") (pintype "passive"))
      (node (ref "R36") (pin "2") (pinfunction "2_2") (pintype "passive"))
    )
    (net (code "41") (name "Net-(OK1-A)") (class "Default")
      (node (ref "OK1") (pin "1") (pinfunction "A_1") (pintype "passive"))
      (node (ref "R1") (pin "1") (pinfunction "1_1") (pintype "passive"))
    )
    (net (code "42") (name "Net-(OK1-C)") (class "Default")
      (node (ref "LED1") (pin "A") (pinfunction "A_A") (pintype "passive"))
      (node (ref "OK1") (pin "2") (pinfunction "C_2") (pintype "passive"))
    )
    (net (code "43") (name "Net-(OK1-EMIT)") (class "Default")
      (node (ref "OK1") (pin "3") (pinfunction "EMIT_3") (pintype "passive"))
      (node (ref "R2") (pin "2") (pinfunction "2_2") (pintype "passive"))
    )
    (net (code "44") (name "Net-(OK2-A)") (class "Default")
      (node (ref "OK2") (pin "1") (pinfunction "A_1") (pintype "passive"))
      (node (ref "R3") (pin "1") (pinfunction "1_1") (pintype "passive"))
    )
    (net (code "45") (name "Net-(OK2-C)") (class "Default")
      (node (ref "LED2") (pin "A") (pinfunction "A_A") (pintype "passive"))
      (node (ref "OK2") (pin "2") (pinfunction "C_2") (pintype "passive"))
    )
    (net (code "46") (name "Net-(OK2-EMIT)") (class "Default")
      (node (ref "OK2") (pin "3") (pinfunction "EMIT_3") (pintype "passive"))
      (node (ref "R4") (pin "2") (pinfunction "2_2") (pintype "passive"))
    )
    (net (code "47") (name "Net-(OK3-A)") (class "Default")
      (node (ref "OK3") (pin "1") (pinfunction "A_1") (pintype "passive"))
      (node (ref "R5") (pin "1") (pinfunction "1_1") (pintype "passive"))
    )
    (net (code "48") (name "Net-(OK3-C)") (class "Default")
      (node (ref "LED3") (pin "A") (pinfunction "A_A") (pintype "passive"))
      (node (ref "OK3") (pin "2") (pinfunction "C_2") (pintype "passive"))
    )
    (net (code "49") (name "Net-(OK3-EMIT)") (class "Default")
      (node (ref "OK3") (pin "3") (pinfunction "EMIT_3") (pintype "passive"))
      (node (ref "R6") (pin "2") (pinfunction "2_2") (pintype "passive"))
    )
    (net (code "50") (name "Net-(OK4-A)") (class "Default")
      (node (ref "OK4") (pin "1") (pinfunction "A_1") (pintype "passive"))
      (node (ref "R7") (pin "1") (pinfunction "1_1") (pintype "passive"))
    )
    (net (code "51") (name "Net-(OK4-C)") (class "Default")
      (node (ref "LED4") (pin "A") (pinfunction "A_A") (pintype "passive"))
      (node (ref "OK4") (pin "2") (pinfunction "C_2") (pintype "passive"))
    )
    (net (code "52") (name "Net-(OK4-EMIT)") (class "Default")
      (node (ref "OK4") (pin "3") (pinfunction "EMIT_3") (pintype "passive"))
      (node (ref "R8") (pin "2") (pinfunction "2_2") (pintype "passive"))
    )
    (net (code "53") (name "Net-(OK5-A)") (class "Default")
      (node (ref "OK5") (pin "1") (pinfunction "A_1") (pintype "passive"))
      (node (ref "R31") (pin "1") (pinfunction "1_1") (pintype "passive"))
    )
    (net (code "54") (name "Net-(OK5-C)") (class "Default")
      (node (ref "LED5") (pin "A") (pinfunction "A_A") (pintype "passive"))
      (node (ref "OK5") (pin "2") (pinfunction "C_2") (pintype "passive"))
    )
    (net (code "55") (name "Net-(OK5-EMIT)") (class "Default")
      (node (ref "OK5") (pin "3") (pinfunction "EMIT_3") (pintype "passive"))
      (node (ref "R32") (pin "2") (pinfunction "2_2") (pintype "passive"))
    )
    (net (code "56") (name "Net-(Q1-B)") (class "Default")
      (node (ref "Q1") (pin "2") (pinfunction "B_2") (pintype "passive"))
      (node (ref "R2") (pin "1") (pinfunction "1_1") (pintype "passive"))
    )
    (net (code "57") (name "Net-(Q1-C)") (class "Default")
      (node (ref "D1") (pin "A") (pinfunction "A_A") (pintype "passive"))
      (node (ref "Q1") (pin "3") (pinfunction "C_3") (pintype "passive"))
      (node (ref "U$13") (pin "2") (pinfunction "2_2") (pintype "bidirectional"))
    )
    (net (code "58") (name "Net-(Q2-B)") (class "Default")
      (node (ref "Q2") (pin "2") (pinfunction "B_2") (pintype "passive"))
      (node (ref "R4") (pin "1") (pinfunction "1_1") (pintype "passive"))
    )
    (net (code "59") (name "Net-(Q2-C)") (class "Default")
      (node (ref "D2") (pin "A") (pinfunction "A_A") (pintype "passive"))
      (node (ref "Q2") (pin "3") (pinfunction "C_3") (pintype "passive"))
      (node (ref "U$2") (pin "2") (pinfunction "2_2") (pintype "bidirectional"))
    )
    (net (code "60") (name "Net-(Q3-B)") (class "Default")
      (node (ref "Q3") (pin "2") (pinfunction "B_2") (pintype "passive"))
      (node (ref "R6") (pin "1") (pinfunction "1_1") (pintype "passive"))
    )
    (net (code "61") (name "Net-(Q3-C)") (class "Default")
      (node (ref "D3") (pin "A") (pinfunction "A_A") (pintype "passive"))
      (node (ref "Q3") (pin "3") (pinfunction "C_3") (pintype "passive"))
      (node (ref "U$3") (pin "2") (pinfunction "2_2") (pintype "bidirectional"))
    )
    (net (code "62") (name "Net-(Q4-B)") (class "Default")
      (node (ref "Q4") (pin "2") (pinfunction "B_2") (pintype "passive"))
      (node (ref "R8") (pin "1") (pinfunction "1_1") (pintype "passive"))
    )
    (net (code "63") (name "Net-(Q4-C)") (class "Default")
      (node (ref "D4") (pin "A") (pinfunction "A_A") (pintype "passive"))
      (node (ref "Q4") (pin "3") (pinfunction "C_3") (pintype "passive"))
      (node (ref "U$4") (pin "2") (pinfunction "2_2") (pintype "bidirectional"))
    )
    (net (code "64") (name "Net-(Q5-B)") (class "Default")
      (node (ref "Q5") (pin "2") (pinfunction "B_2") (pintype "passive"))
      (node (ref "R32") (pin "1") (pinfunction "1_1") (pintype "passive"))
    )
    (net (code "65") (name "Net-(Q5-C)") (class "Default")
      (node (ref "D13") (pin "A") (pinfunction "A_A") (pintype "passive"))
      (node (ref "Q5") (pin "3") (pinfunction "C_3") (pintype "passive"))
      (node (ref "U$18") (pin "2") (pinfunction "2_2") (pintype "bidirectional"))
    )
    (net (code "66") (name "Net-(R35-Pad1)") (class "Default")
      (node (ref "R35") (pin "1") (pinfunction "1_1") (pintype "passive"))
      (node (ref "U$1") (pin "28") (pinfunction "28_28") (pintype "bidirectional"))
    )
    (net (code "67") (name "Net-(R36-Pad1)") (class "Default")
      (node (ref "R36") (pin "1") (pinfunction "1_1") (pintype "passive"))
      (node (ref "U$1") (pin "29") (pinfunction "29_29") (pintype "bidirectional"))
    )
    (net (code "68") (name "Net-(U2-ADDR)") (class "Default")
      (node (ref "R24") (pin "1") (pinfunction "1_1") (pintype "passive"))
      (node (ref "U2") (pin "1") (pinfunction "ADDR_1") (pintype "bidirectional"))
    )
    (net (code "69") (name "Net-(U2-ALERT)") (class "Default")
      (node (ref "R23") (pin "2") (pinfunction "2_2") (pintype "passive"))
      (node (ref "U2") (pin "2") (pinfunction "ALERT_2") (pintype "bidirectional"))
    )
    (net (code "70") (name "Net-(U3-ALERT)") (class "Default")
      (node (ref "R27") (pin "2") (pinfunction "2_2") (pintype "passive"))
      (node (ref "U3") (pin "2") (pinfunction "ALERT_2") (pintype "bidirectional"))
    )
    (net (code "71") (name "Net-(U4-ALERT)") (class "Default")
      (node (ref "R30") (pin "2") (pinfunction "2_2") (pintype "passive"))
      (node (ref "U4") (pin "2") (pinfunction "ALERT_2") (pintype "bidirectional"))
    )
    (net (code "72") (name "OSV-4_SIG") (class "Default")
      (node (ref "U$2") (pin "NO") (pinfunction "NO_NO") (pintype "bidirectional"))
      (node (ref "X2") (pin "P$14") (pinfunction "14_P$14") (pintype "passive"))
    )
    (net (code "73") (name "OSV-5_SIG") (class "Default")
      (node (ref "U$3") (pin "NO") (pinfunction "NO_NO") (pintype "bidirectional"))
      (node (ref "X2") (pin "P$15") (pinfunction "15_P$15") (pintype "passive"))
    )
    (net (code "74") (name "OTC1+") (class "Default")
      (node (ref "FB1") (pin "1") (pinfunction "P$1_1") (pintype "bidirectional"))
      (node (ref "OTC1") (pin "1") (pinfunction "1_1") (pintype "passive"))
    )
    (net (code "75") (name "OTC1-") (class "Default")
      (node (ref "FB2") (pin "1") (pinfunction "P$1_1") (pintype "bidirectional"))
      (node (ref "OTC1") (pin "2") (pinfunction "2_2") (pintype "passive"))
    )
    (net (code "76") (name "OTC1_CS") (class "Default")
      (node (ref "D5") (pin "C") (pinfunction "C_C") (pintype "passive"))
      (node (ref "U$1") (pin "26") (pinfunction "26_26") (pintype "bidirectional"))
    )
    (net (code "77") (name "OTC2+") (class "Default")
      (node (ref "FB3") (pin "1") (pinfunction "P$1_1") (pintype "bidirectional"))
      (node (ref "OTC2") (pin "1") (pinfunction "1_1") (pintype "passive"))
    )
    (net (code "78") (name "OTC2-") (class "Default")
      (node (ref "FB4") (pin "1") (pinfunction "P$1_1") (pintype "bidirectional"))
      (node (ref "OTC2") (pin "2") (pinfunction "2_2") (pintype "passive"))
    )
    (net (code "79") (name "OTC2_CS") (class "Default")
      (node (ref "D7") (pin "C") (pinfunction "C_C") (pintype "passive"))
      (node (ref "U$1") (pin "24") (pinfunction "24_24") (pintype "bidirectional"))
    )
    (net (code "80") (name "OTC3+") (class "Default")
      (node (ref "FB5") (pin "1") (pinfunction "P$1_1") (pintype "bidirectional"))
      (node (ref "OTC3") (pin "1") (pinfunction "1_1") (pintype "passive"))
    )
    (net (code "81") (name "OTC3-") (class "Default")
      (node (ref "FB6") (pin "1") (pinfunction "P$1_1") (pintype "bidirectional"))
      (node (ref "OTC3") (pin "2") (pinfunction "2_2") (pintype "passive"))
    )
    (net (code "82") (name "OTC3_CS") (class "Default")
      (node (ref "D9") (pin "C") (pinfunction "C_C") (pintype "passive"))
      (node (ref "U$1") (pin "25") (pinfunction "25_25") (pintype "bidirectional"))
    )
    (net (code "83") (name "OTC4+") (class "Default")
      (node (ref "FB7") (pin "1") (pinfunction "P$1_1") (pintype "bidirectional"))
      (node (ref "OTC4") (pin "1") (pinfunction "1_1") (pintype "passive"))
    )
    (net (code "84") (name "OTC4-") (class "Default")
      (node (ref "FB8") (pin "1") (pinfunction "P$1_1") (pintype "bidirectional"))
      (node (ref "OTC4") (pin "2") (pinfunction "2_2") (pintype "passive"))
    )
    (net (code "85") (name "OTC4_CS") (class "Default")
      (node (ref "D11") (pin "C") (pinfunction "C_C") (pintype "passive"))
      (node (ref "U$1") (pin "27") (pinfunction "27_27") (pintype "bidirectional"))
    )
    (net (code "86") (name "PT1_OPT1") (class "Default")
      (node (ref "U2") (pin "4") (pinfunction "AIN0_4") (pintype "bidirectional"))
      (node (ref "X1") (pin "P$20") (pinfunction "20_P$20") (pintype "passive"))
    )
    (net (code "87") (name "PT2_OPT2") (class "Default")
      (node (ref "U2") (pin "5") (pinfunction "AIN1_5") (pintype "bidirectional"))
      (node (ref "X1") (pin "P$19") (pinfunction "19_P$19") (pintype "passive"))
    )
    (net (code "88") (name "PT3_OPT3") (class "Default")
      (node (ref "U2") (pin "6") (pinfunction "AIN2_6") (pintype "bidirectional"))
      (node (ref "X1") (pin "P$17") (pinfunction "17_P$17") (pintype "passive"))
    )
    (net (code "89") (name "PT4_NPT1") (class "Default")
      (node (ref "U2") (pin "7") (pinfunction "AIN3_7") (pintype "bidirectional"))
      (node (ref "X1") (pin "P$16") (pinfunction "16_P$16") (pintype "passive"))
    )
    (net (code "90") (name "PT5_NPT2") (class "Default")
      (node (ref "U3") (pin "4") (pinfunction "AIN0_4") (pintype "bidirectional"))
      (node (ref "X1") (pin "P$14") (pinfunction "14_P$14") (pintype "passive"))
    )
    (net (code "91") (name "PT6") (class "Default")
      (node (ref "U3") (pin "5") (pinfunction "AIN1_5") (pintype "bidirectional"))
      (node (ref "X1") (pin "P$13") (pinfunction "13_P$13") (pintype "passive"))
    )
    (net (code "92") (name "PT7") (class "Default")
      (node (ref "U3") (pin "6") (pinfunction "AIN2_6") (pintype "bidirectional"))
      (node (ref "X1") (pin "P$11") (pinfunction "11_P$11") (pintype "passive"))
    )
    (net (code "93") (name "PT8") (class "Default")
      (node (ref "U3") (pin "7") (pinfunction "AIN3_7") (pintype "bidirectional"))
      (node (ref "X3") (pin "P$20") (pinfunction "20_P$20") (pintype "passive"))
    )
    (net (code "94") (name "SCALE+") (class "Default")
      (node (ref "U4") (pin "6") (pinfunction "AIN2_6") (pintype "bidirectional"))
      (node (ref "X3") (pin "P$16") (pinfunction "16_P$16") (pintype "passive"))
    )
    (net (code "95") (name "SCALE-") (class "Default")
      (node (ref "U4") (pin "7") (pinfunction "AIN3_7") (pintype "bidirectional"))
      (node (ref "X3") (pin "P$15") (pinfunction "15_P$15") (pintype "passive"))
    )
    (net (code "96") (name "SCL") (class "Default")
      (node (ref "IC5") (pin "16") (pinfunction "SCL_16") (pintype "bidirectional"))
      (node (ref "R19") (pin "2") (pinfunction "2_2") (pintype "passive"))
      (node (ref "R25") (pin "2") (pinfunction "2_2") (pintype "passive"))
      (node (ref "R28") (pin "2") (pinfunction "2_2") (pintype "passive"))
      (node (ref "R33") (pin "2") (pinfunction "2_2") (pintype "passive"))
      (node (ref "U$1") (pin "19/A5/SCL") (pinfunction "19/A5/SCL_19/A5/SCL") (pintype "bidirectional"))
      (node (ref "U2") (pin "10") (pinfunction "SCL_10") (pintype "bidirectional"))
      (node (ref "U3") (pin "10") (pinfunction "SCL_10") (pintype "bidirectional"))
      (node (ref "U4") (pin "10") (pinfunction "SCL_10") (pintype "bidirectional"))
    )
    (net (code "97") (name "SDA") (class "Default")
      (node (ref "IC5") (pin "15") (pinfunction "SDA_15") (pintype "bidirectional"))
      (node (ref "R22") (pin "2") (pinfunction "2_2") (pintype "passive"))
      (node (ref "R26") (pin "2") (pinfunction "2_2") (pintype "passive"))
      (node (ref "R29") (pin "2") (pinfunction "2_2") (pintype "passive"))
      (node (ref "R34") (pin "2") (pinfunction "2_2") (pintype "passive"))
      (node (ref "U$1") (pin "18/A4/SDA") (pinfunction "18/A4/SDA_18/A4/SDA") (pintype "bidirectional"))
      (node (ref "U2") (pin "9") (pinfunction "SDA_9") (pintype "bidirectional"))
      (node (ref "U3") (pin "9") (pinfunction "SDA_9") (pintype "bidirectional"))
      (node (ref "U4") (pin "1") (pinfunction "ADDR_1") (pintype "bidirectional"))
      (node (ref "U4") (pin "9") (pinfunction "SDA_9") (pintype "bidirectional"))
    )
    (net (code "98") (name "SOL1_WSV2") (class "Default")
      (node (ref "LED1") (pin "C") (pinfunction "C_C") (pintype "passive"))
      (node (ref "U$1") (pin "5") (pinfunction "5_5") (pintype "bidirectional"))
    )
    (net (code "99") (name "SOL2_OSV4") (class "Default")
      (node (ref "LED2") (pin "C") (pinfunction "C_C") (pintype "passive"))
      (node (ref "U$1") (pin "4/CANRX") (pinfunction "4/CANRX_4/CANRX") (pintype "bidirectional"))
    )
    (net (code "100") (name "SOL3_OSV5") (class "Default")
      (node (ref "LED3") (pin "C") (pinfunction "C_C") (pintype "passive"))
      (node (ref "U$1") (pin "3/CANTX") (pinfunction "3/CANTX_3/CANTX") (pintype "bidirectional"))
    )
    (net (code "101") (name "SOL4_NSV2") (class "Default")
      (node (ref "LED4") (pin "C") (pinfunction "C_C") (pintype "passive"))
      (node (ref "U$1") (pin "2") (pinfunction "2_2") (pintype "bidirectional"))
    )
    (net (code "102") (name "TC_DO") (class "Default")
      (node (ref "IC1") (pin "7") (pinfunction "DO_7") (pintype "output"))
      (node (ref "IC2") (pin "7") (pinfunction "DO_7") (pintype "output"))
      (node (ref "IC3") (pin "7") (pinfunction "DO_7") (pintype "output"))
      (node (ref "IC4") (pin "7") (pinfunction "DO_7") (pintype "output"))
      (node (ref "U$1") (pin "23/A9") (pinfunction "23/A9_23/A9") (pintype "bidirectional"))
    )
    (net (code "103") (name "TC_SCK") (class "Default")
      (node (ref "D10") (pin "C") (pinfunction "C_C") (pintype "passive"))
      (node (ref "D12") (pin "C") (pinfunction "C_C") (pintype "passive"))
      (node (ref "D6") (pin "C") (pinfunction "C_C") (pintype "passive"))
      (node (ref "D8") (pin "C") (pinfunction "C_C") (pintype "passive"))
      (node (ref "U$1") (pin "22/A8") (pinfunction "22/A8_22/A8") (pintype "bidirectional"))
    )
    (net (code "104") (name "WSV-2_SIG") (class "Default")
      (node (ref "U$13") (pin "NO") (pinfunction "NO_NO") (pintype "bidirectional"))
      (node (ref "X2") (pin "P$13") (pinfunction "13_P$13") (pintype "passive"))
    )
    (net (code "105") (name "XBEE_RX") (class "Default")
      (node (ref "U$1") (pin "1/TX") (pinfunction "1/TX_1/TX") (pintype "bidirectional"))
      (node (ref "XB1") (pin "3") (pinfunction "DIN/~{CONFIG}_3") (pintype "input"))
    )
    (net (code "106") (name "XBEE_TX") (class "Default")
      (node (ref "U$1") (pin "0/RX") (pinfunction "0/RX_0/RX") (pintype "bidirectional"))
      (node (ref "XB1") (pin "2") (pinfunction "DOUT_2") (pintype "output"))
    )
    (net (code "107") (name "unconnected-(IC5-NC-Pad5)") (class "Default")
      (node (ref "IC5") (pin "5") (pinfunction "NC_5") (pintype "no_connect"))
    )
    (net (code "108") (name "unconnected-(IC5-NC1-Pad6)") (class "Default")
      (node (ref "IC5") (pin "6") (pinfunction "NC1_6") (pintype "no_connect"))
    )
    (net (code "109") (name "unconnected-(IC5-NC2-Pad7)") (class "Default")
      (node (ref "IC5") (pin "7") (pinfunction "NC2_7") (pintype "no_connect"))
    )
    (net (code "110") (name "unconnected-(IC5-NC3-Pad8)") (class "Default")
      (node (ref "IC5") (pin "8") (pinfunction "NC3_8") (pintype "no_connect"))
    )
    (net (code "111") (name "unconnected-(IC5-NC4-Pad9)") (class "Default")
      (node (ref "IC5") (pin "9") (pinfunction "NC4_9") (pintype "no_connect"))
    )
    (net (code "112") (name "unconnected-(IC5-NC5-Pad10)") (class "Default")
      (node (ref "IC5") (pin "10") (pinfunction "NC5_10") (pintype "no_connect"))
    )
    (net (code "113") (name "unconnected-(IC5-NC6-Pad11)") (class "Default")
      (node (ref "IC5") (pin "11") (pinfunction "NC6_11") (pintype "no_connect"))
    )
    (net (code "114") (name "unconnected-(IC5-NC7-Pad12)") (class "Default")
      (node (ref "IC5") (pin "12") (pinfunction "NC7_12") (pintype "no_connect"))
    )
    (net (code "115") (name "unconnected-(U$1-A21{slash}DAC0-Pad21{slash}DAC0)") (class "Default")
      (node (ref "U$1") (pin "21/DAC0") (pinfunction "A21/DAC0_21/DAC0") (pintype "bidirectional"))
    )
    (net (code "116") (name "unconnected-(U$1-Pad3V3_2)") (class "Default")
      (node (ref "U$1") (pin "3V3_2") (pinfunction "3V3_2_3V3_2") (pintype "bidirectional"))
    )
    (net (code "117") (name "unconnected-(U$1-Pad3V3_LO)") (class "Default")
      (node (ref "U$1") (pin "3V3_LO") (pinfunction "3V3_LO_3V3_LO") (pintype "bidirectional"))
    )
    (net (code "118") (name "unconnected-(U$1-Pad11{slash}MOSI)") (class "Default")
      (node (ref "U$1") (pin "11/MOSI") (pinfunction "11/MOSI_11/MOSI") (pintype "bidirectional"))
    )
    (net (code "119") (name "unconnected-(U$1-Pad12{slash}MISO)") (class "Default")
      (node (ref "U$1") (pin "12/MISO") (pinfunction "12/MISO_12/MISO") (pintype "bidirectional"))
    )
    (net (code "120") (name "unconnected-(U$1-Pad13{slash}SCK)") (class "Default")
      (node (ref "U$1") (pin "13/SCK") (pinfunction "13/SCK_13/SCK") (pintype "bidirectional"))
    )
    (net (code "121") (name "unconnected-(U$1-Pad14{slash}A0)") (class "Default")
      (node (ref "U$1") (pin "14/A0") (pinfunction "14/A0_14/A0") (pintype "bidirectional"))
    )
    (net (code "122") (name "unconnected-(U$1-Pad15{slash}A1)") (class "Default")
      (node (ref "U$1") (pin "15/A1") (pinfunction "15/A1_15/A1") (pintype "bidirectional"))
    )
    (net (code "123") (name "unconnected-(U$1-Pad16{slash}A2)") (class "Default")
      (node (ref "U$1") (pin "16/A2") (pinfunction "16/A2_16/A2") (pintype "bidirectional"))
    )
    (net (code "124") (name "unconnected-(U$1-Pad17{slash}A3)") (class "Default")
      (node (ref "U$1") (pin "17/A3") (pinfunction "17/A3_17/A3") (pintype "bidirectional"))
    )
    (net (code "125") (name "unconnected-(U$1-Pad20{slash}A6)") (class "Default")
      (node (ref "U$1") (pin "20/A6") (pinfunction "20/A6_20/A6") (pintype "bidirectional"))
    )
    (net (code "126") (name "unconnected-(U$1-Pad21{slash}A7)") (class "Default")
      (node (ref "U$1") (pin "21/A7") (pinfunction "21/A7_21/A7") (pintype "bidirectional"))
    )
    (net (code "127") (name "unconnected-(U$1-Pad30)") (class "Default")
      (node (ref "U$1") (pin "30") (pinfunction "30_30") (pintype "bidirectional"))
    )
    (net (code "128") (name "unconnected-(U$1-Pad31{slash}A12)") (class "Default")
      (node (ref "U$1") (pin "31/A12") (pinfunction "31/A12_31/A12") (pintype "bidirectional"))
    )
    (net (code "129") (name "unconnected-(U$1-Pad32{slash}A13)") (class "Default")
      (node (ref "U$1") (pin "32/A13") (pinfunction "32/A13_32/A13") (pintype "bidirectional"))
    )
    (net (code "130") (name "unconnected-(U$1-Pad33{slash}A14)") (class "Default")
      (node (ref "U$1") (pin "33/A14") (pinfunction "33/A14_33/A14") (pintype "bidirectional"))
    )
    (net (code "131") (name "unconnected-(U$1-Pad34{slash}A15)") (class "Default")
      (node (ref "U$1") (pin "34/A15") (pinfunction "34/A15_34/A15") (pintype "bidirectional"))
    )
    (net (code "132") (name "unconnected-(U$1-Pad35{slash}A16)") (class "Default")
      (node (ref "U$1") (pin "35/A16") (pinfunction "35/A16_35/A16") (pintype "bidirectional"))
    )
    (net (code "133") (name "unconnected-(U$1-Pad36{slash}A17)") (class "Default")
      (node (ref "U$1") (pin "36/A17") (pinfunction "36/A17_36/A17") (pintype "bidirectional"))
    )
    (net (code "134") (name "unconnected-(U$1-Pad37{slash}A18)") (class "Default")
      (node (ref "U$1") (pin "37/A18") (pinfunction "37/A18_37/A18") (pintype "bidirectional"))
    )
    (net (code "135") (name "unconnected-(U$1-Pad38{slash}A19)") (class "Default")
      (node (ref "U$1") (pin "38/A19") (pinfunction "38/A19_38/A19") (pintype "bidirectional"))
    )
    (net (code "136") (name "unconnected-(U$1-Pad39{slash}A20)") (class "Default")
      (node (ref "U$1") (pin "39/A20") (pinfunction "39/A20_39/A20") (pintype "bidirectional"))
    )
    (net (code "137") (name "unconnected-(U$1-PadA10)") (class "Default")
      (node (ref "U$1") (pin "A10") (pinfunction "A10_A10") (pintype "bidirectional"))
    )
    (net (code "138") (name "unconnected-(U$1-PadA11)") (class "Default")
      (node (ref "U$1") (pin "A11") (pinfunction "A11_A11") (pintype "bidirectional"))
    )
    (net (code "139") (name "unconnected-(U$1-PadA22{slash}DAC1)") (class "Default")
      (node (ref "U$1") (pin "A22/DAC1") (pinfunction "A22/DAC1_A22/DAC1") (pintype "bidirectional"))
    )
    (net (code "140") (name "unconnected-(U$1-PadAREF)") (class "Default")
      (node (ref "U$1") (pin "AREF") (pinfunction "AREF_AREF") (pintype "bidirectional"))
    )
    (net (code "141") (name "unconnected-(U$1-PadGND3)") (class "Default")
      (node (ref "U$1") (pin "GND3") (pinfunction "GND3_GND3") (pintype "bidirectional"))
    )
    (net (code "142") (name "unconnected-(U$1-PadPROG)") (class "Default")
      (node (ref "U$1") (pin "PROG") (pinfunction "PROG_PROG") (pintype "bidirectional"))
    )
    (net (code "143") (name "unconnected-(U$1-PadRESET)") (class "Default")
      (node (ref "U$1") (pin "RESET") (pinfunction "RESET_RESET") (pintype "bidirectional"))
    )
    (net (code "144") (name "unconnected-(U$1-PadU5V)") (class "Default")
      (node (ref "U$1") (pin "U5V") (pinfunction "U5V_U5V") (pintype "bidirectional"))
    )
    (net (code "145") (name "unconnected-(U$1-PadUD+)") (class "Default")
      (node (ref "U$1") (pin "UD+") (pinfunction "UD+_UD+") (pintype "bidirectional"))
    )
    (net (code "146") (name "unconnected-(U$1-PadUD-)") (class "Default")
      (node (ref "U$1") (pin "UD-") (pinfunction "UD-_UD-") (pintype "bidirectional"))
    )
    (net (code "147") (name "unconnected-(U$1-PadUGND1)") (class "Default")
      (node (ref "U$1") (pin "UGND1") (pinfunction "UGND1_UGND1") (pintype "bidirectional"))
    )
    (net (code "148") (name "unconnected-(U$1-PadUGND2)") (class "Default")
      (node (ref "U$1") (pin "UGND2") (pinfunction "UGND2_UGND2") (pintype "bidirectional"))
    )
    (net (code "149") (name "unconnected-(U$1-PadVBAT)") (class "Default")
      (node (ref "U$1") (pin "VBAT") (pinfunction "VBAT_VBAT") (pintype "bidirectional"))
    )
    (net (code "150") (name "unconnected-(U$1-PadVUSB)") (class "Default")
      (node (ref "U$1") (pin "VUSB") (pinfunction "VUSB_VUSB") (pintype "bidirectional"))
    )
    (net (code "151") (name "unconnected-(U$2-PadNC)") (class "Default")
      (node (ref "U$2") (pin "NC") (pinfunction "NC_NC") (pintype "bidirectional"))
    )
    (net (code "152") (name "unconnected-(U$3-PadNC)") (class "Default")
      (node (ref "U$3") (pin "NC") (pinfunction "NC_NC") (pintype "bidirectional"))
    )
    (net (code "153") (name "unconnected-(U$4-PadNC)") (class "Default")
      (node (ref "U$4") (pin "NC") (pinfunction "NC_NC") (pintype "bidirectional"))
    )
    (net (code "154") (name "unconnected-(U$13-PadNC)") (class "Default")
      (node (ref "U$13") (pin "NC") (pinfunction "NC_NC") (pintype "bidirectional"))
    )
    (net (code "155") (name "unconnected-(U$18-PadNC)") (class "Default")
      (node (ref "U$18") (pin "NC") (pinfunction "NC_NC") (pintype "bidirectional"))
    )
    (net (code "156") (name "unconnected-(X3-1-PadP$1)") (class "Default")
      (node (ref "X3") (pin "P$1") (pinfunction "1_P$1") (pintype "passive"))
    )
    (net (code "157") (name "unconnected-(X3-2-PadP$2)") (class "Default")
      (node (ref "X3") (pin "P$2") (pinfunction "2_P$2") (pintype "passive"))
    )
    (net (code "158") (name "unconnected-(X3-3-PadP$3)") (class "Default")
      (node (ref "X3") (pin "P$3") (pinfunction "3_P$3") (pintype "passive"))
    )
    (net (code "159") (name "unconnected-(X3-4-PadP$4)") (class "Default")
      (node (ref "X3") (pin "P$4") (pinfunction "4_P$4") (pintype "passive"))
    )
    (net (code "160") (name "unconnected-(X3-11-PadP$11)") (class "Default")
      (node (ref "X3") (pin "P$11") (pinfunction "11_P$11") (pintype "passive"))
    )
    (net (code "161") (name "unconnected-(X3-12-PadP$12)") (class "Default")
      (node (ref "X3") (pin "P$12") (pinfunction "12_P$12") (pintype "passive"))
    )
    (net (code "162") (name "unconnected-(X3-13-PadP$13)") (class "Default")
      (node (ref "X3") (pin "P$13") (pinfunction "13_P$13") (pintype "passive"))
    )
    (net (code "163") (name "unconnected-(X3-14-PadP$14)") (class "Default")
      (node (ref "X3") (pin "P$14") (pinfunction "14_P$14") (pintype "passive"))
    )
    (net (code "164") (name "unconnected-(XB1-AD0{slash}DIO0-Pad20)") (class "Default")
      (node (ref "XB1") (pin "20") (pinfunction "AD0/DIO0_20") (pintype "bidirectional"))
    )
    (net (code "165") (name "unconnected-(XB1-AD1{slash}DIO1-Pad19)") (class "Default")
      (node (ref "XB1") (pin "19") (pinfunction "AD1/DIO1_19") (pintype "bidirectional"))
    )
    (net (code "166") (name "unconnected-(XB1-AD2{slash}DIO2-Pad18)") (class "Default")
      (node (ref "XB1") (pin "18") (pinfunction "AD2/DIO2_18") (pintype "bidirectional"))
    )
    (net (code "167") (name "unconnected-(XB1-ASSOC{slash}AD5{slash}DIO5-Pad15)") (class "Default")
      (node (ref "XB1") (pin "15") (pinfunction "ASSOC/AD5/DIO5_15") (pintype "bidirectional"))
    )
    (net (code "168") (name "unconnected-(XB1-CD{slash}DOUT_EN{slash}DO8-Pad4)") (class "Default")
      (node (ref "XB1") (pin "4") (pinfunction "CD/DOUT_EN/DO8_4") (pintype "output"))
    )
    (net (code "169") (name "unconnected-(XB1-COORD_SEL{slash}AD3{slash}DIO3-Pad17)") (class "Default")
      (node (ref "XB1") (pin "17") (pinfunction "COORD_SEL/AD3/DIO3_17") (pintype "bidirectional"))
    )
    (net (code "170") (name "unconnected-(XB1-ON{slash}~{SLEEP}-Pad13)") (class "Default")
      (node (ref "XB1") (pin "13") (pinfunction "ON/~{SLEEP}_13") (pintype "output"))
    )
    (net (code "171") (name "unconnected-(XB1-PWM0{slash}RSSI-Pad6)") (class "Default")
      (node (ref "XB1") (pin "6") (pinfunction "PWM0/RSSI_6") (pintype "output"))
    )
    (net (code "172") (name "unconnected-(XB1-RF_TX{slash}AD4{slash}DIO4-Pad11)") (class "Default")
      (node (ref "XB1") (pin "11") (pinfunction "RF_TX/AD4/DIO4_11") (pintype "bidirectional"))
    )
    (net (code "173") (name "unconnected-(XB1-VREF-Pad14)") (class "Default")
      (node (ref "XB1") (pin "14") (pinfunction "VREF_14") (pintype "input"))
    )
    (net (code "174") (name "unconnected-(XB1-~{CTS}{slash}DIO7-Pad12)") (class "Default")
      (node (ref "XB1") (pin "12") (pinfunction "~{CTS}/DIO7_12") (pintype "bidirectional"))
    )
    (net (code "175") (name "unconnected-(XB1-~{DTR}{slash}SLEEP_RQ{slash}DI8-Pad9)") (class "Default")
      (node (ref "XB1") (pin "9") (pinfunction "~{DTR}/SLEEP_RQ/DI8_9") (pintype "bidirectional"))
    )
    (net (code "176") (name "unconnected-(XB1-~{RESET}-Pad5)") (class "Default")
      (node (ref "XB1") (pin "5") (pinfunction "~{RESET}_5") (pintype "input"))
    )
    (net (code "177") (name "unconnected-(XB1-~{RTS}{slash}AD6{slash}DIO6-Pad16)") (class "Default")
      (node (ref "XB1") (pin "16") (pinfunction "~{RTS}/AD6/DIO6_16") (pintype "bidirectional"))
    )
  )
)
